# Mainboard_User_LED3_Connector.net
KiCad netlist of a schematic drawn in Altium Designer
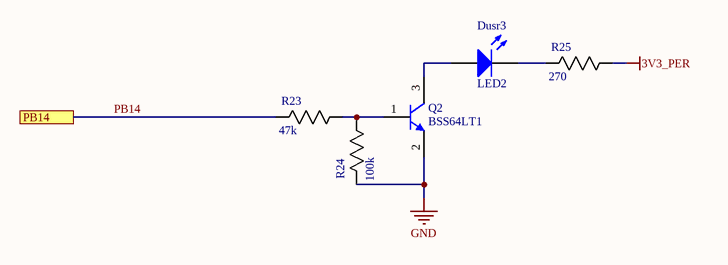
[diagram p0: Mainboard_User LED3 Connector.SchDoc]

(export (version "E")
  (design (tool "Eeschema 10.0.6"))
  (components
    (comp (ref "Dusr3")
      (value "LED2")
      (footprint "3.2X1.6X1.1")
      (description "Typical RED, GREEN, YELLOW, AMBER GaAs LED")
      (libsource (lib "AltiumLibraries") (part "LED RED SMD"))
    )
    (comp (ref "Q2")
      (value "BSS64LT1")
      (footprint "ONSC-SOT-23-3-318-08_V")
      (description "Driver Transistor, NPN Silicon, 3-Pin SOT-23, Tape and Reel")
      (fields (field (name "MANUFACTURER") "On Semiconductor"))
      (libsource (lib "Altium Content Vault") (part "ONSC-NPN-B1E2C3-3"))
    )
    (comp (ref "R23")
      (value "47k")
      (footprint "0805")
      (description "RES SMD 47K OHM 1% 1/8W 0805")
      (fields (field (name "TOLERANCE") "1%"))
      (libsource (lib "AltiumLibraries") (part "RES 47k 1/8W - 1%"))
    )
    (comp (ref "R24")
      (value "100k")
      (footprint "0805")
      (description "RES SMD 100K OHM 1% 1/8W 0805")
      (fields (field (name "TOLERANCE") "1%"))
      (libsource (lib "AltiumLibraries") (part "RES 100k 1/8W - 1%"))
    )
    (comp (ref "R25")
      (value "270")
      (footprint "0805")
      (description "RES SMD 270 OHM 5% 1/8W 0805")
      (fields (field (name "TOLERANCE") "5%"))
      (libsource (lib "AltiumLibraries") (part "RES 270.0 1/8W"))
    )
  )
  (nets
    (net (code "1") (name "/PB14") (class "Default")
      (node (ref "R23") (pin "2") (pinfunction "R2_2") (pintype "passive"))
    )
    (net (code "2") (name "3V3_PER") (class "Default")
      (node (ref "R25") (pin "1") (pinfunction "R1_1") (pintype "passive"))
    )
    (net (code "3") (name "GND") (class "Default")
      (node (ref "Q2") (pin "2") (pinfunction "E_2") (pintype "passive"))
      (node (ref "R24") (pin "2") (pinfunction "R2_2") (pintype "passive"))
    )
    (net (code "4") (name "Net-(Dusr3-A)") (class "Default")
      (node (ref "Dusr3") (pin "1") (pinfunction "A_1") (pintype "passive"))
      (node (ref "Q2") (pin "3") (pinfunction "C_3") (pintype "passive"))
    )
    (net (code "5") (name "Net-(Dusr3-K)") (class "Default")
      (node (ref "Dusr3") (pin "2") (pinfunction "K_2") (pintype "passive"))
      (node (ref "R25") (pin "2") (pinfunction "R2_2") (pintype "passive"))
    )
    (net (code "6") (name "Net-(Q2-B)") (class "Default")
      (node (ref "Q2") (pin "1") (pinfunction "B_1") (pintype "passive"))
      (node (ref "R23") (pin "1") (pinfunction "R1_1") (pintype "passive"))
      (node (ref "R24") (pin "1") (pinfunction "R1_1") (pintype "passive"))
    )
  )
)
